# main.net
KiCad netlist of a schematic drawn in Altium Designer
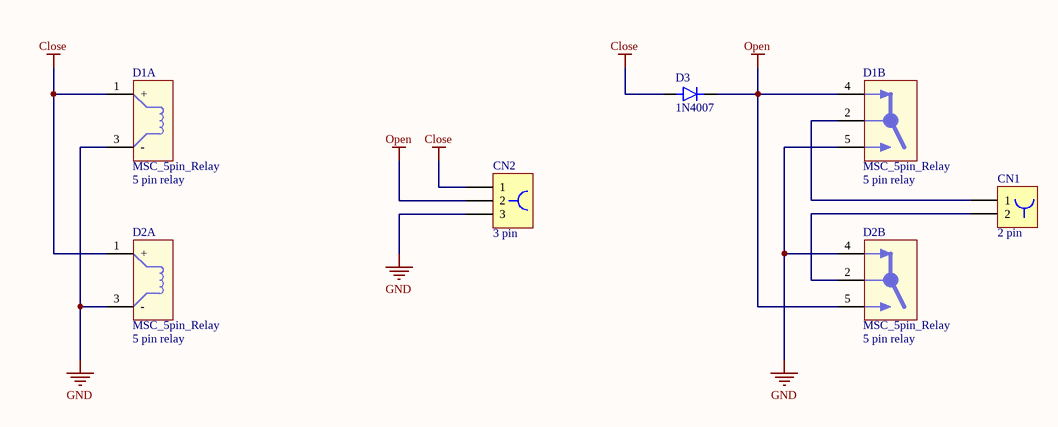
[diagram p0: main.SchDoc]

(export (version "E")
  (design (tool "Eeschema 10.0.6"))
  (components
    (comp (ref "CN1")
      (value "CN_1X2F")
      (footprint "CN_WURTH_691216510002")
      (description "WURTH ELEKTRONIK - 691216510002 - T/BLOCK, 5.08MM")
      (fields (field (name "VALUE1") "2 pin") (field (name "MANUFACTURER") "Wurth"))
      (libsource (lib "DSW_Lib") (part "CN_1X2F"))
    )
    (comp (ref "CN2")
      (value "CN_1X3F")
      (footprint "CN_WURTH_691216510003")
      (description "WURTH ELEKTRONIK 691216510003 - T/BLOCK, 5,08mm 3W")
      (fields (field (name "VALUE1") "3 pin") (field (name "MANUFACTURER") "Wurth"))
      (libsource (lib "DSW_Lib") (part "CN_1X3F"))
    )
    (comp (ref "D1")
      (value "MSC_5pin_Relay")
      (footprint "MSC_SRA-12VDC-CL")
      (fields (field (name "VALUE1") "5 pin relay") (field (name "MANUFACTURER") "SRA"))
      (libsource (lib "DSW_Lib") (part "MSC_5pin_Relay"))
    )
    (comp (ref "D2")
      (value "MSC_5pin_Relay")
      (footprint "MSC_SRA-12VDC-CL")
      (fields (field (name "VALUE1") "5 pin relay") (field (name "MANUFACTURER") "SRA"))
      (libsource (lib "DSW_Lib") (part "MSC_5pin_Relay"))
    )
    (comp (ref "D3")
      (value "DIO")
      (footprint "DIO_Fairchild_1N4007")
      (description "Rectifiers Vr/1000V Io/1A")
      (fields (field (name "VALUE1") "1N4007") (field (name "MANUFACTURER") "Fairchild"))
      (libsource (lib "DSW_Lib") (part "DIO"))
    )
  )
  (nets
    (net (code "1") (name "Close") (class "Default")
      (node (ref "CN2") (pin "1") (pinfunction "1_1") (pintype "passive"))
      (node (ref "D1") (pin "1") (pinfunction "+_1") (pintype "power_in"))
      (node (ref "D2") (pin "1") (pinfunction "+_1") (pintype "power_in"))
      (node (ref "D3") (pin "2") (pinfunction "A_2") (pintype "passive"))
    )
    (net (code "2") (name "GND") (class "Default")
      (node (ref "CN2") (pin "3") (pinfunction "3_3") (pintype "passive"))
      (node (ref "D1") (pin "3") (pinfunction "-_3") (pintype "power_in"))
      (node (ref "D1") (pin "5") (pinfunction "5_5") (pintype "power_in"))
      (node (ref "D2") (pin "3") (pinfunction "-_3") (pintype "power_in"))
      (node (ref "D2") (pin "4") (pinfunction "4_4") (pintype "power_in"))
    )
    (net (code "3") (name "Net-(CN1-Pad1)") (class "Default")
      (node (ref "CN1") (pin "1") (pinfunction "1_1") (pintype "passive"))
      (node (ref "D1") (pin "2") (pinfunction "2_2") (pintype "power_in"))
    )
    (net (code "4") (name "Net-(CN1-Pad2)") (class "Default")
      (node (ref "CN1") (pin "2") (pinfunction "2_2") (pintype "passive"))
      (node (ref "D2") (pin "2") (pinfunction "2_2") (pintype "power_in"))
    )
    (net (code "5") (name "Open") (class "Default")
      (node (ref "CN2") (pin "2") (pinfunction "2_2") (pintype "passive"))
      (node (ref "D1") (pin "4") (pinfunction "4_4") (pintype "power_in"))
      (node (ref "D2") (pin "5") (pinfunction "5_5") (pintype "power_in"))
      (node (ref "D3") (pin "1") (pinfunction "K_1") (pintype "passive"))
    )
  )
)
